# module_3_GROVE.net
KiCad netlist of a schematic drawn in Altium Designer
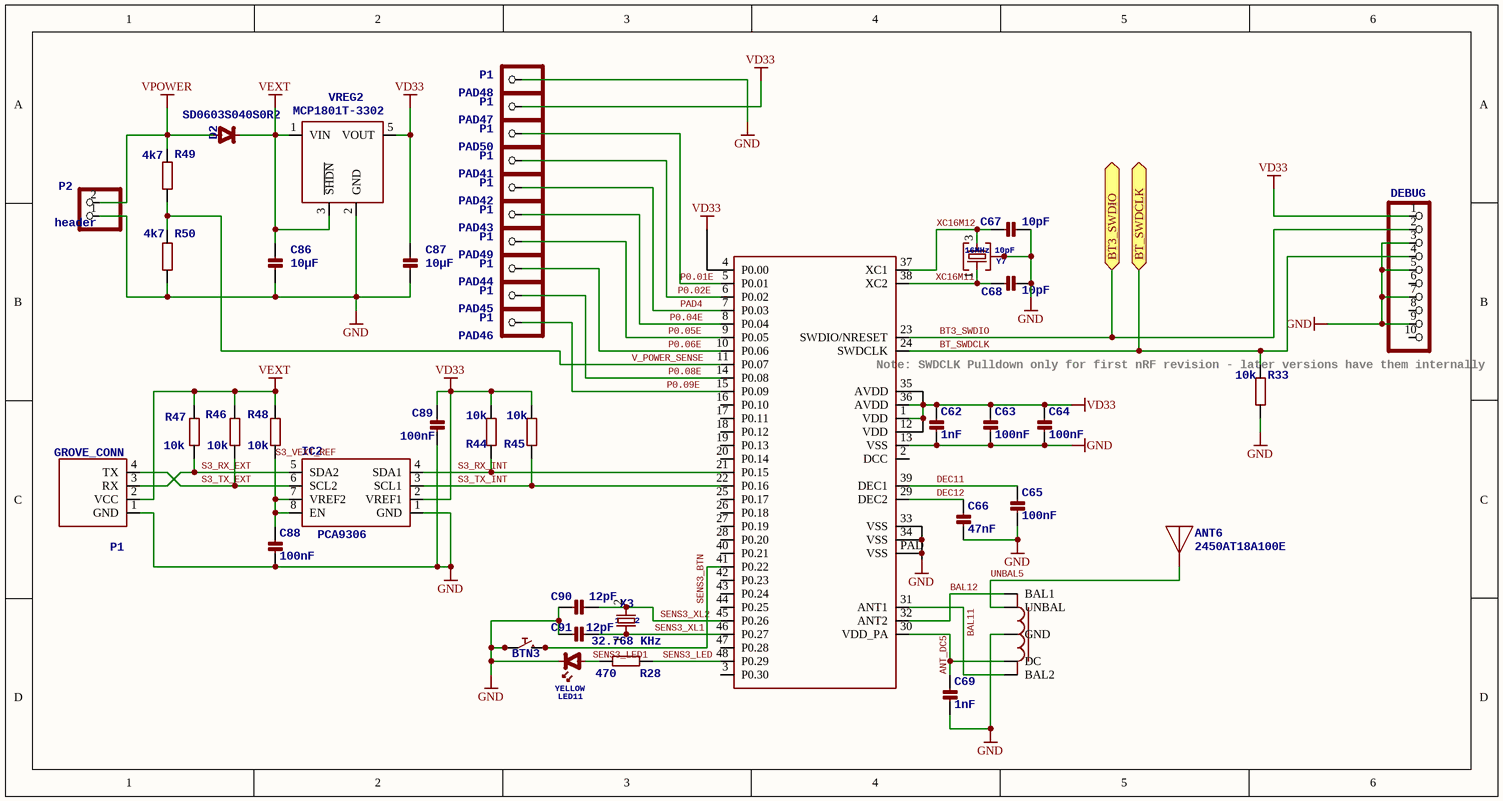
[diagram p0: module 3_GROVE.SchDoc]

(export (version "E")
  (design (tool "Eeschema 10.0.6"))
  (components
    (comp (ref "ANT6")
      (value "2450AT18A100E")
      (footprint "1206_MINIMELF_COMBO")
      (description "2.45 GHz Antenna")
      (libsource (lib "WunderBar_v101") (part "ANTENNA_MONOPOLE1206"))
    )
    (comp (ref "BALUN3")
      (value "2450BM14A0002T")
      (footprint "6-PIN-0603")
      (description "2.45 GHz Impedance Matched Balun-Filter")
      (libsource (lib "WunderBar_v101") (part "BALUN"))
    )
    (comp (ref "BT3")
      (value "NRF51822QFN48")
      (footprint "QFN48_EP")
      (description "Nordic Bluetooth 4.0 low energy modul")
      (libsource (lib "WunderBar_v101") (part "NRF51822QFN48"))
    )
    (comp (ref "BTN3")
      (value "Tact Sw 4.6x2.8")
      (footprint "CK-KMR2")
      (description "Push button")
      (libsource (lib "WunderBar_v101") (part "PUSHBUTTONKMR2XX"))
    )
    (comp (ref "C62")
      (value "1nF")
      (footprint "0402")
      (description "Ceramic Capacitor")
      (libsource (lib "WunderBar_v101") (part "CAP_CERAMIC0402"))
    )
    (comp (ref "C63")
      (value "100nF")
      (footprint "0402")
      (description "Ceramic Capacitor")
      (libsource (lib "WunderBar_v101") (part "CAP_CERAMIC0402"))
    )
    (comp (ref "C64")
      (value "100nF")
      (footprint "0402")
      (description "Ceramic Capacitor")
      (libsource (lib "WunderBar_v101") (part "CAP_CERAMIC0402"))
    )
    (comp (ref "C65")
      (value "100nF")
      (footprint "0402")
      (description "Ceramic Capacitor")
      (libsource (lib "WunderBar_v101") (part "CAP_CERAMIC0402"))
    )
    (comp (ref "C66")
      (value "47nF")
      (footprint "0402")
      (description "Ceramic Capacitor")
      (libsource (lib "WunderBar_v101") (part "CAP_CERAMIC0402"))
    )
    (comp (ref "C67")
      (value "10pF")
      (footprint "0402")
      (description "Ceramic Capacitor")
      (libsource (lib "") (part "CAP_CERAMIC0402_1"))
    )
    (comp (ref "C68")
      (value "10pF")
      (footprint "0402")
      (description "Ceramic Capacitor")
      (libsource (lib "") (part "CAP_CERAMIC0402_1"))
    )
    (comp (ref "C69")
      (value "1nF")
      (footprint "0402")
      (description "Ceramic Capacitor")
      (libsource (lib "WunderBar_v101") (part "CAP_CERAMIC0402"))
    )
    (comp (ref "C86")
      (value "10µF")
      (footprint "0603")
      (description "Ceramic Capacitor")
      (libsource (lib "WunderBar_v101") (part "CAP_CERAMIC0603"))
    )
    (comp (ref "C87")
      (value "10µF")
      (footprint "0603")
      (description "Ceramic Capacitor")
      (libsource (lib "WunderBar_v101") (part "CAP_CERAMIC0603"))
    )
    (comp (ref "C88")
      (value "100nF")
      (footprint "0402")
      (description "Ceramic Capacitor")
      (libsource (lib "WunderBar_v101") (part "CAP_CERAMIC0402"))
    )
    (comp (ref "C89")
      (value "100nF")
      (footprint "0402")
      (description "Ceramic Capacitor")
      (libsource (lib "WunderBar_v101") (part "CAP_CERAMIC0402"))
    )
    (comp (ref "C90")
      (value "12pF")
      (footprint "0402")
      (description "Ceramic Capacitor")
      (libsource (lib "") (part "CAP_CERAMIC0402_1"))
    )
    (comp (ref "C91")
      (value "12pF")
      (footprint "0402")
      (description "Ceramic Capacitor")
      (libsource (lib "") (part "CAP_CERAMIC0402_1"))
    )
    (comp (ref "D2")
      (value "SD0603S040S0R2")
      (footprint "0603_POLAR")
      (description "Shottky diode 40V 0.2A")
      (libsource (lib "WunderBar_v101") (part "DIODE0603"))
    )
    (comp (ref "DEBUG3")
      (value "DEBUG")
      (footprint "2X05_SMT")
      (description "cortex DEBUG connector")
      (libsource (lib "WunderBar_v101") (part "HEADER-2X5SMD-1.27MM"))
    )
    (comp (ref "IC2")
      (value "PCA9306")
      (footprint "US8")
      (description "I2C bidirectional level translator")
      (libsource (lib "WunderBar_v101") (part "PCA9306US8"))
    )
    (comp (ref "LED11")
      (value "YELLOW")
      (footprint "0402_POLAR")
      (description "LED common")
      (libsource (lib "WunderBar_v101") (part "LED0402"))
    )
    (comp (ref "P1")
      (value "GROVE_CONN")
      (footprint "GROVE-CONN-TH")
      (description "Seeed Grove 4-pin 2mm connector")
      (libsource (lib "WunderBar_v102") (part "GROVE_CONNV"))
    )
    (comp (ref "P2")
      (value "header")
      (footprint "1X02_ROUND")
      (description "PIN HEADER")
      (libsource (lib "WunderBar_v101") (part "HEADER-1X2ROUND"))
    )
    (comp (ref "PAD41")
      (value "P1")
      (footprint "PCB_MEDIUM_RECT_PAD")
      (description "<b>PIN HEADER</b>")
      (libsource (lib "WunderBar_v101") (part "HEADER-1X1SMD_MEDIUM"))
    )
    (comp (ref "PAD42")
      (value "P1")
      (footprint "PCB_MEDIUM_RECT_PAD")
      (description "<b>PIN HEADER</b>")
      (libsource (lib "WunderBar_v101") (part "HEADER-1X1SMD_MEDIUM"))
    )
    (comp (ref "PAD43")
      (value "P1")
      (footprint "PCB_MEDIUM_RECT_PAD")
      (description "<b>PIN HEADER</b>")
      (libsource (lib "WunderBar_v101") (part "HEADER-1X1SMD_MEDIUM"))
    )
    (comp (ref "PAD44")
      (value "P1")
      (footprint "PCB_MEDIUM_RECT_PAD")
      (description "<b>PIN HEADER</b>")
      (libsource (lib "WunderBar_v101") (part "HEADER-1X1SMD_MEDIUM"))
    )
    (comp (ref "PAD45")
      (value "P1")
      (footprint "PCB_MEDIUM_RECT_PAD")
      (description "<b>PIN HEADER</b>")
      (libsource (lib "WunderBar_v101") (part "HEADER-1X1SMD_MEDIUM"))
    )
    (comp (ref "PAD46")
      (value "P1")
      (footprint "PCB_MEDIUM_RECT_PAD")
      (description "<b>PIN HEADER</b>")
      (libsource (lib "WunderBar_v101") (part "HEADER-1X1SMD_MEDIUM"))
    )
    (comp (ref "PAD47")
      (value "P1")
      (footprint "PCB_MEDIUM_RECT_PAD")
      (description "<b>PIN HEADER</b>")
      (libsource (lib "WunderBar_v101") (part "HEADER-1X1SMD_MEDIUM"))
    )
    (comp (ref "PAD48")
      (value "P1")
      (footprint "PCB_MEDIUM_RECT_PAD")
      (description "<b>PIN HEADER</b>")
      (libsource (lib "WunderBar_v101") (part "HEADER-1X1SMD_MEDIUM"))
    )
    (comp (ref "PAD49")
      (value "P1")
      (footprint "PCB_MEDIUM_RECT_PAD")
      (description "<b>PIN HEADER</b>")
      (libsource (lib "WunderBar_v101") (part "HEADER-1X1SMD_MEDIUM"))
    )
    (comp (ref "PAD50")
      (value "P1")
      (footprint "PCB_MEDIUM_RECT_PAD")
      (description "<b>PIN HEADER</b>")
      (libsource (lib "WunderBar_v101") (part "HEADER-1X1SMD_MEDIUM"))
    )
    (comp (ref "R28")
      (value "470")
      (footprint "0402")
      (description "RESISTOR")
      (libsource (lib "WunderBar_v101") (part "R-EU_0402"))
    )
    (comp (ref "R33")
      (value "10k")
      (footprint "0402")
      (description "RESISTOR")
      (libsource (lib "WunderBar_v101") (part "R-EU_0402"))
    )
    (comp (ref "R44")
      (value "10k")
      (footprint "0402")
      (description "RESISTOR")
      (libsource (lib "WunderBar_v101") (part "R-EU_0402"))
    )
    (comp (ref "R45")
      (value "10k")
      (footprint "0402")
      (description "RESISTOR")
      (libsource (lib "WunderBar_v101") (part "R-EU_0402"))
    )
    (comp (ref "R46")
      (value "10k")
      (footprint "0402")
      (description "RESISTOR")
      (libsource (lib "WunderBar_v101") (part "R-EU_0402"))
    )
    (comp (ref "R47")
      (value "10k")
      (footprint "0402")
      (description "RESISTOR")
      (libsource (lib "WunderBar_v101") (part "R-EU_0402"))
    )
    (comp (ref "R48")
      (value "10k")
      (footprint "0402")
      (description "RESISTOR")
      (libsource (lib "WunderBar_v101") (part "R-EU_0402"))
    )
    (comp (ref "R49")
      (value "4k7")
      (footprint "0402")
      (description "RESISTOR")
      (libsource (lib "WunderBar_v101") (part "R-EU_0402"))
    )
    (comp (ref "R50")
      (value "4k7")
      (footprint "0402")
      (description "RESISTOR")
      (libsource (lib "WunderBar_v101") (part "R-EU_0402"))
    )
    (comp (ref "VREG2")
      (value "MCP1801T-3302")
      (footprint "SOT-23-5")
      (description "Microchip LDO")
      (libsource (lib "WunderBar_v101") (part "MCP180XSOT-23-5"))
    )
    (comp (ref "X3")
      (value "32.768 KHz")
      (footprint "1206_MINIMELF_COMBO")
      (description "CL05C120JB5")
      (fields (field (name "1") "1") (field (name "2") "2"))
      (libsource (lib "WunderBar_v101") (part "CRYSTAL1206"))
    )
    (comp (ref "Y7")
      (value "16MHz 10pF")
      (footprint "CRYSTAL25X20")
      (description "16MHz crystal 2.5x2mm")
      (libsource (lib "WunderBar_v101") (part "CRYSTAL_WITH_GROUND25X20"))
    )
  )
  (nets
    (net (code "1") (name "/ANT_DC5") (class "Default")
      (node (ref "BALUN3") (pin "5") (pinfunction "DC_5") (pintype "power_in"))
      (node (ref "BT3") (pin "30") (pinfunction "VDD_PA_30") (pintype "passive"))
      (node (ref "C69") (pin "1") (pinfunction "1_1") (pintype "passive"))
    )
    (net (code "2") (name "/BAL11") (class "Default")
      (node (ref "BALUN3") (pin "4") (pinfunction "BAL2_4") (pintype "passive"))
      (node (ref "BT3") (pin "31") (pinfunction "ANT1_31") (pintype "passive"))
    )
    (net (code "3") (name "/BAL12") (class "Default")
      (node (ref "BALUN3") (pin "3") (pinfunction "BAL1_3") (pintype "passive"))
      (node (ref "BT3") (pin "32") (pinfunction "ANT2_32") (pintype "passive"))
    )
    (net (code "4") (name "/BT3_SWDIO") (class "Default")
      (node (ref "BT3") (pin "23") (pinfunction "SWDIO/NRESET_23") (pintype "passive"))
      (node (ref "DEBUG3") (pin "2") (pinfunction "2_2") (pintype "passive"))
    )
    (net (code "5") (name "/BT_SWDCLK") (class "Default")
      (node (ref "BT3") (pin "24") (pinfunction "SWDCLK_24") (pintype "passive"))
      (node (ref "DEBUG3") (pin "4") (pinfunction "4_4") (pintype "passive"))
      (node (ref "R33") (pin "2") (pinfunction "2_2") (pintype "passive"))
    )
    (net (code "6") (name "/DEC11") (class "Default")
      (node (ref "BT3") (pin "39") (pinfunction "DEC1_39") (pintype "passive"))
      (node (ref "C65") (pin "1") (pinfunction "1_1") (pintype "passive"))
    )
    (net (code "7") (name "/DEC12") (class "Default")
      (node (ref "BT3") (pin "29") (pinfunction "DEC2_29") (pintype "passive"))
      (node (ref "C66") (pin "1") (pinfunction "1_1") (pintype "passive"))
    )
    (net (code "8") (name "/P0.01E") (class "Default")
      (node (ref "BT3") (pin "5") (pinfunction "P0.01_5") (pintype "passive"))
      (node (ref "PAD50") (pin "1") (pinfunction "1_1") (pintype "passive"))
    )
    (net (code "9") (name "/P0.02E") (class "Default")
      (node (ref "BT3") (pin "6") (pinfunction "P0.02_6") (pintype "passive"))
      (node (ref "PAD41") (pin "1") (pinfunction "1_1") (pintype "passive"))
    )
    (net (code "10") (name "/P0.04E") (class "Default")
      (node (ref "BT3") (pin "8") (pinfunction "P0.04_8") (pintype "passive"))
      (node (ref "PAD43") (pin "1") (pinfunction "1_1") (pintype "passive"))
    )
    (net (code "11") (name "/P0.05E") (class "Default")
      (node (ref "BT3") (pin "9") (pinfunction "P0.05_9") (pintype "passive"))
      (node (ref "PAD49") (pin "1") (pinfunction "1_1") (pintype "passive"))
    )
    (net (code "12") (name "/P0.06E") (class "Default")
      (node (ref "BT3") (pin "10") (pinfunction "P0.06_10") (pintype "passive"))
      (node (ref "PAD44") (pin "1") (pinfunction "1_1") (pintype "passive"))
    )
    (net (code "13") (name "/P0.08E") (class "Default")
      (node (ref "BT3") (pin "14") (pinfunction "P0.08_14") (pintype "passive"))
      (node (ref "PAD45") (pin "1") (pinfunction "1_1") (pintype "passive"))
    )
    (net (code "14") (name "/P0.09E") (class "Default")
      (node (ref "BT3") (pin "15") (pinfunction "P0.09_15") (pintype "passive"))
      (node (ref "PAD46") (pin "1") (pinfunction "1_1") (pintype "passive"))
    )
    (net (code "15") (name "/PAD4") (class "Default")
      (node (ref "BT3") (pin "7") (pinfunction "P0.03_7") (pintype "passive"))
      (node (ref "PAD42") (pin "1") (pinfunction "1_1") (pintype "passive"))
    )
    (net (code "16") (name "/S3_RX_EXT") (class "Default")
      (node (ref "IC2") (pin "5") (pinfunction "SDA2_5") (pintype "passive"))
      (node (ref "P1") (pin "3") (pinfunction "RX_3") (pintype "passive"))
      (node (ref "R47") (pin "1") (pinfunction "1_1") (pintype "passive"))
    )
    (net (code "17") (name "/S3_RX_INT") (class "Default")
      (node (ref "BT3") (pin "21") (pinfunction "P0.15_21") (pintype "passive"))
      (node (ref "IC2") (pin "4") (pinfunction "SDA1_4") (pintype "passive"))
      (node (ref "R44") (pin "1") (pinfunction "1_1") (pintype "passive"))
    )
    (net (code "18") (name "/S3_TX_EXT") (class "Default")
      (node (ref "IC2") (pin "6") (pinfunction "SCL2_6") (pintype "passive"))
      (node (ref "P1") (pin "4") (pinfunction "TX_4") (pintype "passive"))
      (node (ref "R46") (pin "1") (pinfunction "1_1") (pintype "passive"))
    )
    (net (code "19") (name "/S3_TX_INT") (class "Default")
      (node (ref "BT3") (pin "22") (pinfunction "P0.16_22") (pintype "passive"))
      (node (ref "IC2") (pin "3") (pinfunction "SCL1_3") (pintype "passive"))
      (node (ref "R45") (pin "1") (pinfunction "1_1") (pintype "passive"))
    )
    (net (code "20") (name "/S3_VEXT_REF") (class "Default")
      (node (ref "C88") (pin "1") (pinfunction "1_1") (pintype "passive"))
      (node (ref "IC2") (pin "7") (pinfunction "VREF2_7") (pintype "passive"))
      (node (ref "IC2") (pin "8") (pinfunction "EN_8") (pintype "passive"))
      (node (ref "R48") (pin "1") (pinfunction "1_1") (pintype "passive"))
    )
    (net (code "21") (name "/SENS3_BTN") (class "Default")
      (node (ref "BT3") (pin "41") (pinfunction "P0.22_41") (pintype "passive"))
      (node (ref "BTN3") (pin "P3") (pinfunction "3_P3") (pintype "passive"))
      (node (ref "BTN3") (pin "P4") (pinfunction "4_P4") (pintype "passive"))
    )
    (net (code "22") (name "/SENS3_LED") (class "Default")
      (node (ref "BT3") (pin "48") (pinfunction "P0.29_48") (pintype "passive"))
      (node (ref "R28") (pin "1") (pinfunction "1_1") (pintype "passive"))
    )
    (net (code "23") (name "/SENS3_LED1") (class "Default")
      (node (ref "LED11") (pin "A") (pinfunction "ANODE_A") (pintype "passive"))
      (node (ref "R28") (pin "2") (pinfunction "2_2") (pintype "passive"))
    )
    (net (code "24") (name "/SENS3_XL1") (class "Default")
      (node (ref "BT3") (pin "46") (pinfunction "P0.27_46") (pintype "passive"))
      (node (ref "C91") (pin "2") (pinfunction "2_2") (pintype "passive"))
      (node (ref "X3") (pin "1") (pinfunction "1_1") (pintype "passive"))
    )
    (net (code "25") (name "/SENS3_XL2") (class "Default")
      (node (ref "BT3") (pin "45") (pinfunction "P0.26_45") (pintype "passive"))
      (node (ref "C90") (pin "2") (pinfunction "2_2") (pintype "passive"))
      (node (ref "X3") (pin "2") (pinfunction "2_2") (pintype "passive"))
    )
    (net (code "26") (name "/UNBAL5") (class "Default")
      (node (ref "ANT6") (pin "1") (pinfunction "ANT_1") (pintype "passive"))
      (node (ref "BALUN3") (pin "1") (pinfunction "UNBAL_1") (pintype "passive"))
    )
    (net (code "27") (name "/V_POWER_SENSE") (class "Default")
      (node (ref "BT3") (pin "11") (pinfunction "P0.07_11") (pintype "passive"))
      (node (ref "R49") (pin "1") (pinfunction "1_1") (pintype "passive"))
      (node (ref "R50") (pin "2") (pinfunction "2_2") (pintype "passive"))
    )
    (net (code "28") (name "/XC16M11") (class "Default")
      (node (ref "BT3") (pin "38") (pinfunction "XC2_38") (pintype "passive"))
      (node (ref "C68") (pin "1") (pinfunction "1_1") (pintype "passive"))
      (node (ref "Y7") (pin "1") (pinfunction "1_1") (pintype "passive"))
    )
    (net (code "29") (name "/XC16M12") (class "Default")
      (node (ref "BT3") (pin "37") (pinfunction "XC1_37") (pintype "passive"))
      (node (ref "C67") (pin "1") (pinfunction "1_1") (pintype "passive"))
      (node (ref "Y7") (pin "3") (pinfunction "3_3") (pintype "passive"))
    )
    (net (code "30") (name "GND") (class "Default")
      (node (ref "BALUN3") (pin "2") (pinfunction "GND_2") (pintype "power_in"))
      (node (ref "BT3") (pin "13") (pinfunction "VSS_13") (pintype "passive"))
      (node (ref "BT3") (pin "33") (pinfunction "VSS_33") (pintype "passive"))
      (node (ref "BT3") (pin "34") (pinfunction "VSS_34") (pintype "passive"))
      (node (ref "BT3") (pin "PAD") (pinfunction "VSS_PAD") (pintype "passive"))
      (node (ref "BTN3") (pin "P1") (pinfunction "1_P1") (pintype "passive"))
      (node (ref "BTN3") (pin "P2") (pinfunction "2_P2") (pintype "passive"))
      (node (ref "C62") (pin "2") (pinfunction "2_2") (pintype "passive"))
      (node (ref "C63") (pin "2") (pinfunction "2_2") (pintype "passive"))
      (node (ref "C64") (pin "2") (pinfunction "2_2") (pintype "passive"))
      (node (ref "C65") (pin "2") (pinfunction "2_2") (pintype "passive"))
      (node (ref "C66") (pin "2") (pinfunction "2_2") (pintype "passive"))
      (node (ref "C67") (pin "2") (pinfunction "2_2") (pintype "passive"))
      (node (ref "C68") (pin "2") (pinfunction "2_2") (pintype "passive"))
      (node (ref "C69") (pin "2") (pinfunction "2_2") (pintype "passive"))
      (node (ref "C86") (pin "2") (pinfunction "P2_2") (pintype "passive"))
      (node (ref "C87") (pin "2") (pinfunction "P2_2") (pintype "passive"))
      (node (ref "C88") (pin "2") (pinfunction "2_2") (pintype "passive"))
      (node (ref "C89") (pin "2") (pinfunction "2_2") (pintype "passive"))
      (node (ref "C90") (pin "1") (pinfunction "1_1") (pintype "passive"))
      (node (ref "C91") (pin "1") (pinfunction "1_1") (pintype "passive"))
      (node (ref "DEBUG3") (pin "3") (pinfunction "3_3") (pintype "passive"))
      (node (ref "DEBUG3") (pin "5") (pinfunction "5_5") (pintype "passive"))
      (node (ref "DEBUG3") (pin "7") (pinfunction "7_7") (pintype "passive"))
      (node (ref "DEBUG3") (pin "9") (pinfunction "9_9") (pintype "passive"))
      (node (ref "IC2") (pin "1") (pinfunction "GND_1") (pintype "passive"))
      (node (ref "LED11") (pin "K") (pinfunction "CATHODE_K") (pintype "passive"))
      (node (ref "P1") (pin "1") (pinfunction "GND_1") (pintype "passive"))
      (node (ref "P2") (pin "1") (pinfunction "1_1") (pintype "passive"))
      (node (ref "PAD48") (pin "1") (pinfunction "1_1") (pintype "passive"))
      (node (ref "R33") (pin "1") (pinfunction "1_1") (pintype "passive"))
      (node (ref "R50") (pin "1") (pinfunction "1_1") (pintype "passive"))
      (node (ref "VREG2") (pin "2") (pinfunction "GND_2") (pintype "power_in"))
      (node (ref "Y7") (pin "2") (pinfunction "2_2") (pintype "power_in"))
      (node (ref "Y7") (pin "4") (pinfunction "4_4") (pintype "power_in"))
    )
    (net (code "31") (name "VD33") (class "Default")
      (node (ref "BT3") (pin "1") (pinfunction "VDD_1") (pintype "passive"))
      (node (ref "BT3") (pin "12") (pinfunction "VDD_12") (pintype "passive"))
      (node (ref "BT3") (pin "35") (pinfunction "AVDD_35") (pintype "passive"))
      (node (ref "BT3") (pin "36") (pinfunction "AVDD_36") (pintype "passive"))
      (node (ref "BT3") (pin "4") (pinfunction "P0.00_4") (pintype "passive"))
      (node (ref "C62") (pin "1") (pinfunction "1_1") (pintype "passive"))
      (node (ref "C63") (pin "1") (pinfunction "1_1") (pintype "passive"))
      (node (ref "C64") (pin "1") (pinfunction "1_1") (pintype "passive"))
      (node (ref "C87") (pin "1") (pinfunction "P1_1") (pintype "passive"))
      (node (ref "C89") (pin "1") (pinfunction "1_1") (pintype "passive"))
      (node (ref "DEBUG3") (pin "1") (pinfunction "1_1") (pintype "passive"))
      (node (ref "IC2") (pin "2") (pinfunction "VREF1_2") (pintype "passive"))
      (node (ref "PAD47") (pin "1") (pinfunction "1_1") (pintype "passive"))
      (node (ref "R44") (pin "2") (pinfunction "2_2") (pintype "passive"))
      (node (ref "R45") (pin "2") (pinfunction "2_2") (pintype "passive"))
      (node (ref "VREG2") (pin "5") (pinfunction "VOUT_5") (pintype "power_in"))
    )
    (net (code "32") (name "VEXT") (class "Default")
      (node (ref "C86") (pin "1") (pinfunction "P1_1") (pintype "passive"))
      (node (ref "D2") (pin "K") (pinfunction "CATHODE_K") (pintype "passive"))
      (node (ref "P1") (pin "2") (pinfunction "VCC_2") (pintype "passive"))
      (node (ref "R46") (pin "2") (pinfunction "2_2") (pintype "passive"))
      (node (ref "R47") (pin "2") (pinfunction "2_2") (pintype "passive"))
      (node (ref "R48") (pin "2") (pinfunction "2_2") (pintype "passive"))
      (node (ref "VREG2") (pin "1") (pinfunction "VIN_1") (pintype "power_in"))
      (node (ref "VREG2") (pin "3") (pinfunction "~{SHDN}_3") (pintype "passive"))
    )
    (net (code "33") (name "VPOWER") (class "Default")
      (node (ref "D2") (pin "A") (pinfunction "ANODE_A") (pintype "passive"))
      (node (ref "P2") (pin "2") (pinfunction "2_2") (pintype "passive"))
      (node (ref "R49") (pin "2") (pinfunction "2_2") (pintype "passive"))
    )
    (net (code "34") (name "unconnected-(BT3-DCC-Pad2)") (class "Default")
      (node (ref "BT3") (pin "2") (pinfunction "DCC_2") (pintype "passive"))
    )
    (net (code "35") (name "unconnected-(BT3-P0.10-Pad16)") (class "Default")
      (node (ref "BT3") (pin "16") (pinfunction "P0.10_16") (pintype "passive"))
    )
    (net (code "36") (name "unconnected-(BT3-P0.11-Pad17)") (class "Default")
      (node (ref "BT3") (pin "17") (pinfunction "P0.11_17") (pintype "passive"))
    )
    (net (code "37") (name "unconnected-(BT3-P0.12-Pad18)") (class "Default")
      (node (ref "BT3") (pin "18") (pinfunction "P0.12_18") (pintype "passive"))
    )
    (net (code "38") (name "unconnected-(BT3-P0.13-Pad19)") (class "Default")
      (node (ref "BT3") (pin "19") (pinfunction "P0.13_19") (pintype "passive"))
    )
    (net (code "39") (name "unconnected-(BT3-P0.14-Pad20)") (class "Default")
      (node (ref "BT3") (pin "20") (pinfunction "P0.14_20") (pintype "passive"))
    )
    (net (code "40") (name "unconnected-(BT3-P0.17-Pad25)") (class "Default")
      (node (ref "BT3") (pin "25") (pinfunction "P0.17_25") (pintype "passive"))
    )
    (net (code "41") (name "unconnected-(BT3-P0.18-Pad26)") (class "Default")
      (node (ref "BT3") (pin "26") (pinfunction "P0.18_26") (pintype "passive"))
    )
    (net (code "42") (name "unconnected-(BT3-P0.19-Pad27)") (class "Default")
      (node (ref "BT3") (pin "27") (pinfunction "P0.19_27") (pintype "passive"))
    )
    (net (code "43") (name "unconnected-(BT3-P0.20-Pad28)") (class "Default")
      (node (ref "BT3") (pin "28") (pinfunction "P0.20_28") (pintype "passive"))
    )
    (net (code "44") (name "unconnected-(BT3-P0.21-Pad40)") (class "Default")
      (node (ref "BT3") (pin "40") (pinfunction "P0.21_40") (pintype "passive"))
    )
    (net (code "45") (name "unconnected-(BT3-P0.23-Pad42)") (class "Default")
      (node (ref "BT3") (pin "42") (pinfunction "P0.23_42") (pintype "passive"))
    )
    (net (code "46") (name "unconnected-(BT3-P0.24-Pad43)") (class "Default")
      (node (ref "BT3") (pin "43") (pinfunction "P0.24_43") (pintype "passive"))
    )
    (net (code "47") (name "unconnected-(BT3-P0.25-Pad44)") (class "Default")
      (node (ref "BT3") (pin "44") (pinfunction "P0.25_44") (pintype "passive"))
    )
    (net (code "48") (name "unconnected-(BT3-P0.28-Pad47)") (class "Default")
      (node (ref "BT3") (pin "47") (pinfunction "P0.28_47") (pintype "passive"))
    )
    (net (code "49") (name "unconnected-(BT3-P0.30-Pad3)") (class "Default")
      (node (ref "BT3") (pin "3") (pinfunction "P0.30_3") (pintype "passive"))
    )
    (net (code "50") (name "unconnected-(DEBUG3-Pad6)") (class "Default")
      (node (ref "DEBUG3") (pin "6") (pinfunction "6_6") (pintype "passive"))
    )
    (net (code "51") (name "unconnected-(DEBUG3-Pad8)") (class "Default")
      (node (ref "DEBUG3") (pin "8") (pinfunction "8_8") (pintype "passive"))
    )
    (net (code "52") (name "unconnected-(DEBUG3-Pad10)") (class "Default")
      (node (ref "DEBUG3") (pin "10") (pinfunction "10_10") (pintype "passive"))
    )
  )
)
